# 08_Camera.net
KiCad netlist of a schematic drawn in Altium Designer
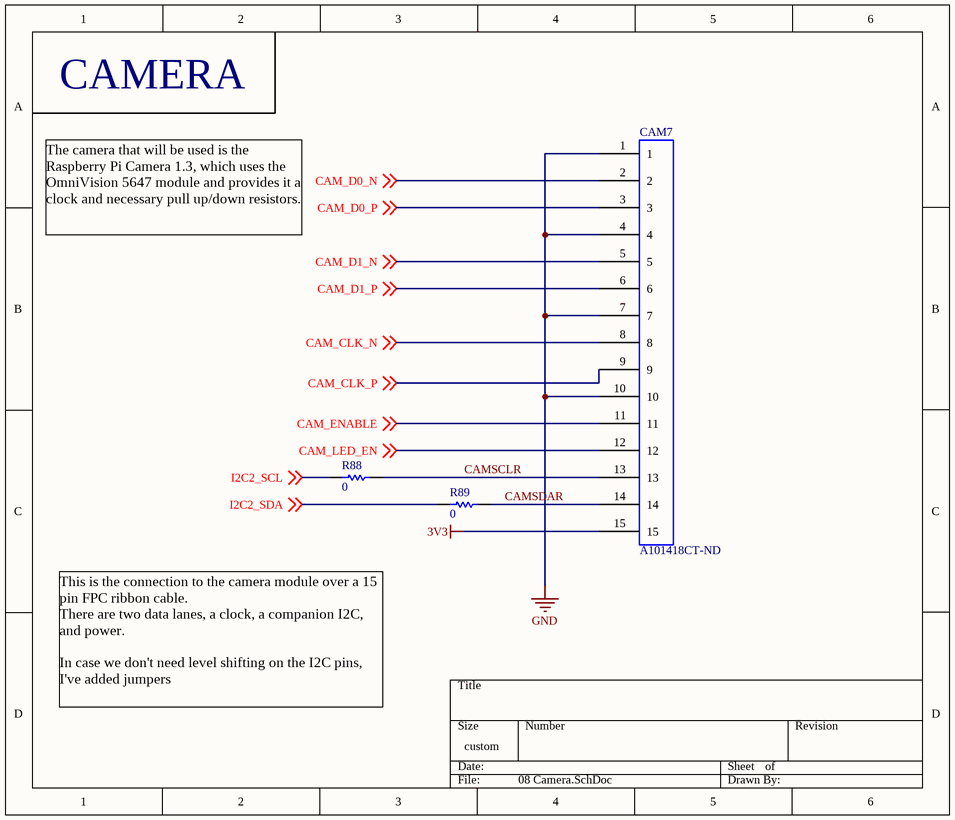
[diagram p0: 08 Camera.SchDoc]

(export (version "E")
  (design (tool "Eeschema 10.0.6"))
  (components
    (comp (ref "CAM7")
      (value "A101418CT-ND")
      (footprint "ZIF_15pin")
      (description "CONN FPC VERT 15POS 1.00MM SMD")
      (fields
        (field (name "MANUFACTURER") "TE Connectivity")
        (field (name "MANUFACTURER PART NUMBER") "1-1734248-5")
      )
      (libsource (lib "schlib_truman") (part "A101418CT-ND"))
    )
    (comp (ref "R88")
      (value "RES_0805_JMP")
      (footprint "RES0805")
      (description "RES, THICK FILM, 0R, 0.125W, 0805")
      (fields
        (field (name "MANUFACTURER") "Yageo")
        (field (name "MANUFACTURER PART NUMBER") "RC0805JR-070RL")
        (field (name "ALTIUM_UNNAMED_1") "0")
      )
      (libsource (lib "schlib_truman") (part "RES_0805_JMP"))
    )
    (comp (ref "R89")
      (value "RES_0805_JMP")
      (footprint "RES0805")
      (description "RES, THICK FILM, 0R, 0.125W, 0805")
      (fields
        (field (name "MANUFACTURER") "Yageo")
        (field (name "MANUFACTURER PART NUMBER") "RC0805JR-070RL")
        (field (name "ALTIUM_UNNAMED_1") "0")
      )
      (libsource (lib "schlib_truman") (part "RES_0805_JMP"))
    )
  )
  (nets
    (net (code "1") (name "/CAMSCLR") (class "Default")
      (node (ref "CAM7") (pin "13") (pinfunction "13_13") (pintype "passive"))
      (node (ref "R88") (pin "2") (pinfunction "2_2") (pintype "passive"))
    )
    (net (code "2") (name "/CAMSDAR") (class "Default")
      (node (ref "CAM7") (pin "14") (pinfunction "14_14") (pintype "passive"))
      (node (ref "R89") (pin "2") (pinfunction "2_2") (pintype "passive"))
    )
    (net (code "3") (name "3V3") (class "Default")
      (node (ref "CAM7") (pin "15") (pinfunction "15_15") (pintype "passive"))
    )
    (net (code "4") (name "CAM_CLK_N") (class "Default")
      (node (ref "CAM7") (pin "8") (pinfunction "8_8") (pintype "passive"))
    )
    (net (code "5") (name "CAM_CLK_P") (class "Default")
      (node (ref "CAM7") (pin "9") (pinfunction "9_9") (pintype "passive"))
    )
    (net (code "6") (name "CAM_D0_N") (class "Default")
      (node (ref "CAM7") (pin "2") (pinfunction "2_2") (pintype "passive"))
    )
    (net (code "7") (name "CAM_D0_P") (class "Default")
      (node (ref "CAM7") (pin "3") (pinfunction "3_3") (pintype "passive"))
    )
    (net (code "8") (name "CAM_D1_N") (class "Default")
      (node (ref "CAM7") (pin "5") (pinfunction "5_5") (pintype "passive"))
    )
    (net (code "9") (name "CAM_D1_P") (class "Default")
      (node (ref "CAM7") (pin "6") (pinfunction "6_6") (pintype "passive"))
    )
    (net (code "10") (name "CAM_ENABLE") (class "Default")
      (node (ref "CAM7") (pin "11") (pinfunction "11_11") (pintype "passive"))
    )
    (net (code "11") (name "CAM_LED_EN") (class "Default")
      (node (ref "CAM7") (pin "12") (pinfunction "12_12") (pintype "passive"))
    )
    (net (code "12") (name "GND") (class "Default")
      (node (ref "CAM7") (pin "1") (pinfunction "1_1") (pintype "passive"))
      (node (ref "CAM7") (pin "10") (pinfunction "10_10") (pintype "passive"))
      (node (ref "CAM7") (pin "4") (pinfunction "4_4") (pintype "passive"))
      (node (ref "CAM7") (pin "7") (pinfunction "7_7") (pintype "passive"))
    )
    (net (code "13") (name "I2C2_SCL") (class "Default")
      (node (ref "R88") (pin "1") (pinfunction "1_1") (pintype "passive"))
    )
    (net (code "14") (name "I2C2_SDA") (class "Default")
      (node (ref "R89") (pin "1") (pinfunction "1_1") (pintype "passive"))
    )
  )
)
